# AstroEQ_SMD_V4_8_EQ5.net
KiCad netlist of a schematic drawn in EAGLE
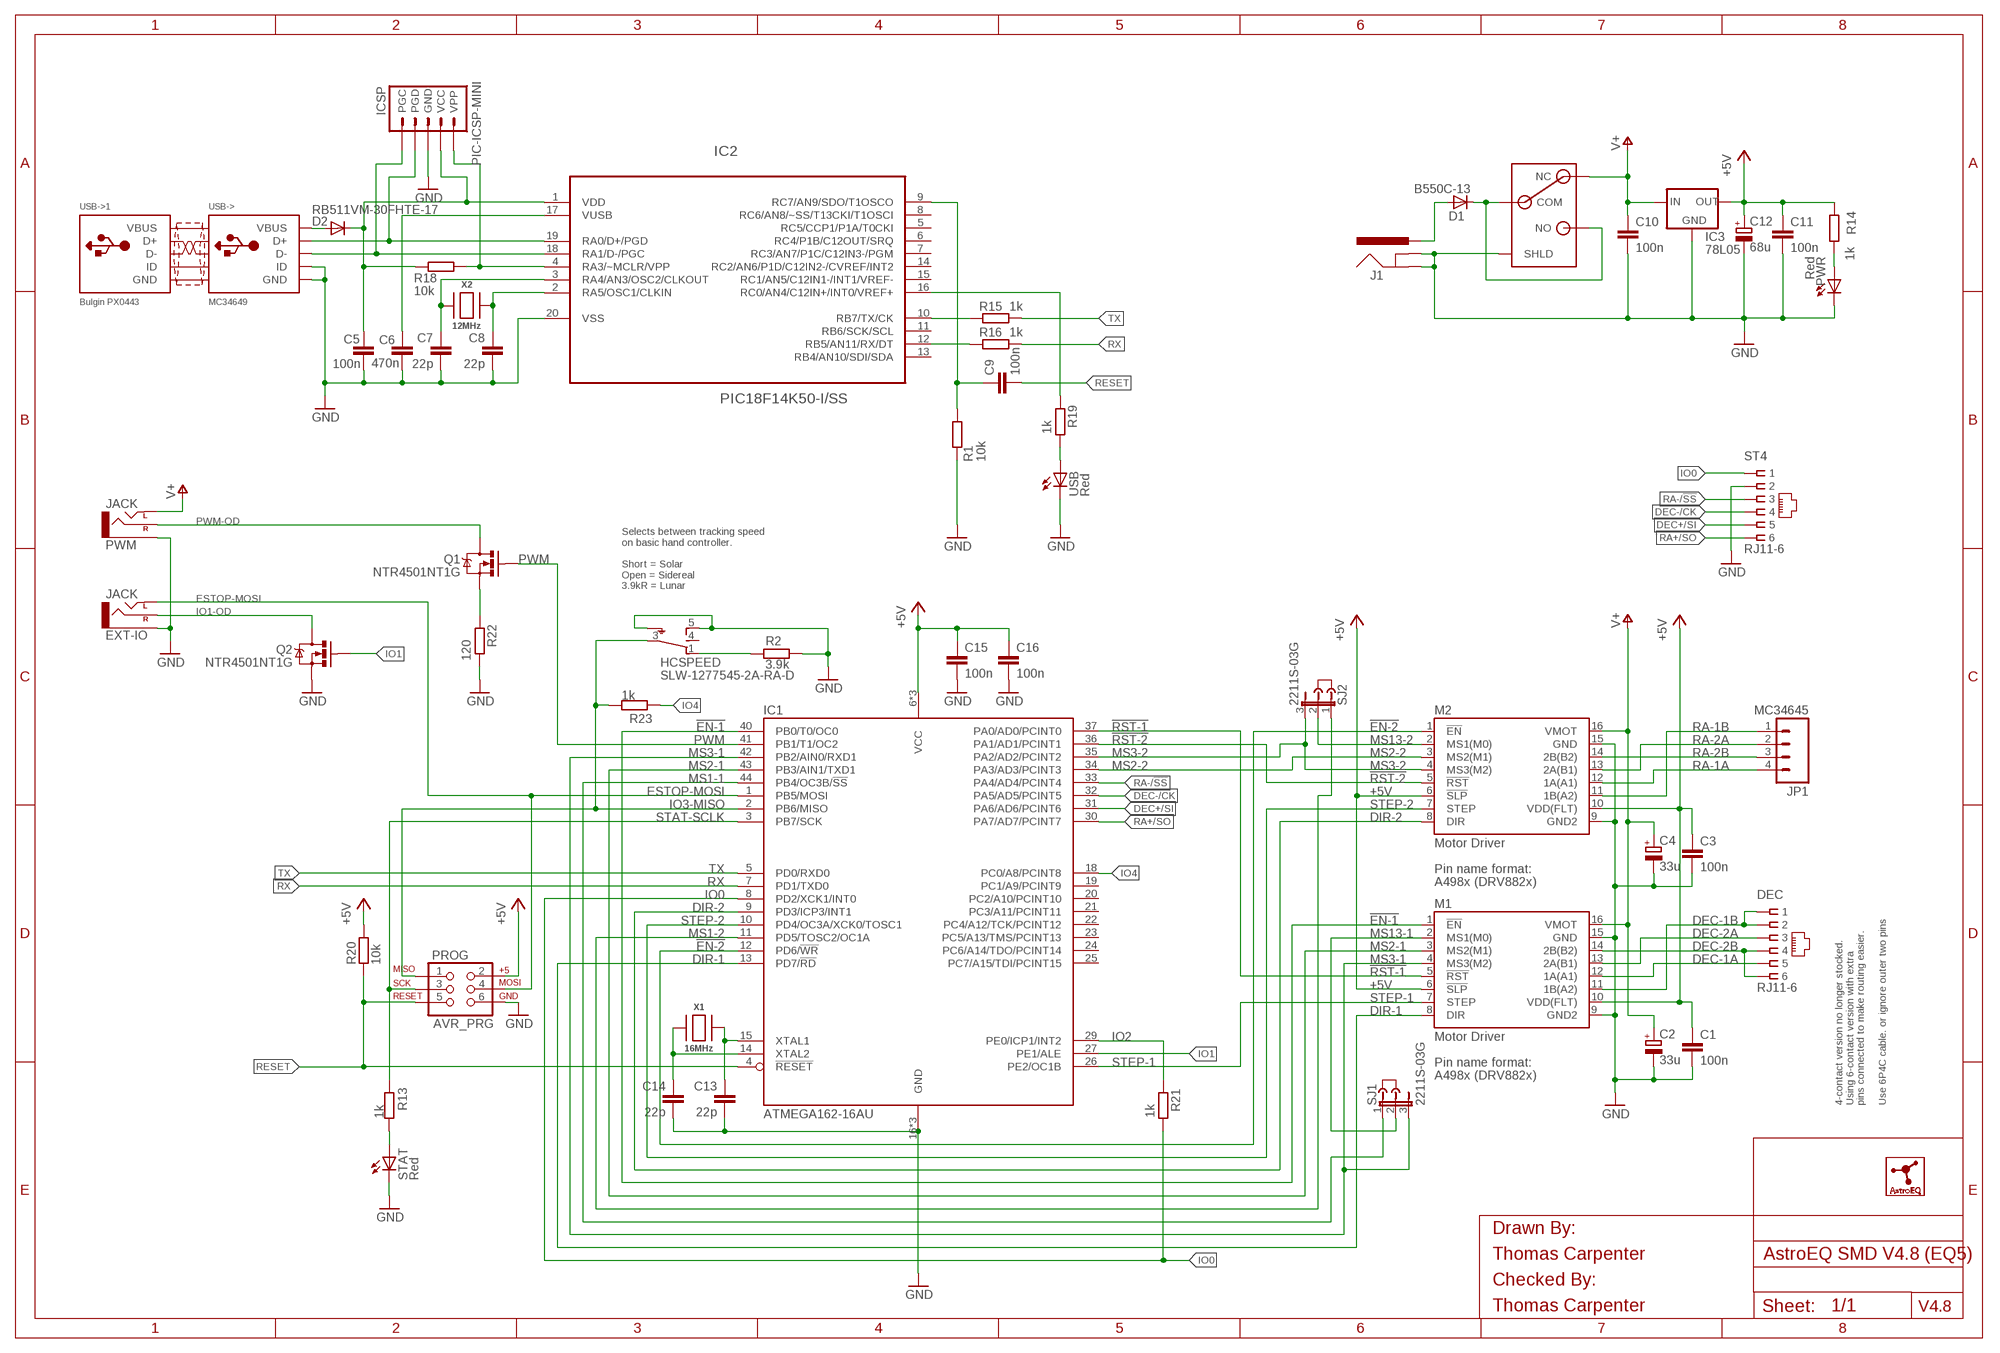
[diagram p0: schematic, sheet 1]

(export (version "E")
  (design (tool "Eeschema 10.0.6"))
  (components
    (comp (ref "C1")
      (value "100n")
      (footprint "eagle-import:C0603")
      (fields (field (name "MF") "MULTICOMP") (field (name "MPN") "MC0603F104Z250CT"))
      (libsource (lib "eagle-import") (part "C-EUC0603"))
    )
    (comp (ref "C2")
      (value "33u")
      (footprint "eagle-import:SMC_C")
      (fields (field (name "MF") "KEMET") (field (name "MPN") "T491C336K025AT"))
      (libsource (lib "eagle-import") (part "CPOL-EUSMCC"))
    )
    (comp (ref "C3")
      (value "100n")
      (footprint "eagle-import:C0603")
      (fields (field (name "MF") "MULTICOMP") (field (name "MPN") "MC0603F104Z250CT"))
      (libsource (lib "eagle-import") (part "C-EUC0603"))
    )
    (comp (ref "C4")
      (value "33u")
      (footprint "eagle-import:SMC_C")
      (fields (field (name "MF") "KEMET") (field (name "MPN") "T491C336K025AT"))
      (libsource (lib "eagle-import") (part "CPOL-EUSMCC"))
    )
    (comp (ref "C5")
      (value "100n")
      (footprint "eagle-import:C0603")
      (fields (field (name "MF") "MULTICOMP") (field (name "MPN") "MC0603F104Z250CT"))
      (libsource (lib "eagle-import") (part "C-EUC0603"))
    )
    (comp (ref "C6")
      (value "470n")
      (footprint "eagle-import:C0603")
      (fields (field (name "MF") "MULTICOMP") (field (name "MPN") "MC0603F474Z160CT"))
      (libsource (lib "eagle-import") (part "C-EUC0603"))
    )
    (comp (ref "C7")
      (value "22p")
      (footprint "eagle-import:C0603")
      (fields (field (name "MF") "MULTICOMP") (field (name "MPN") "MC0603N220J500CT"))
      (libsource (lib "eagle-import") (part "C-EUC0603"))
    )
    (comp (ref "C8")
      (value "22p")
      (footprint "eagle-import:C0603")
      (fields (field (name "MF") "MULTICOMP") (field (name "MPN") "MC0603N220J500CT"))
      (libsource (lib "eagle-import") (part "C-EUC0603"))
    )
    (comp (ref "C9")
      (value "100n")
      (footprint "eagle-import:C0603")
      (fields (field (name "MF") "MULTICOMP") (field (name "MPN") "MC0603F104Z250CT"))
      (libsource (lib "eagle-import") (part "C-EUC0603"))
    )
    (comp (ref "C10")
      (value "100n")
      (footprint "eagle-import:C0603")
      (fields (field (name "MF") "MULTICOMP") (field (name "MPN") "MC0603F104Z250CT"))
      (libsource (lib "eagle-import") (part "C-EUC0603"))
    )
    (comp (ref "C11")
      (value "100n")
      (footprint "eagle-import:C0603")
      (fields (field (name "MF") "MULTICOMP") (field (name "MPN") "MC0603F104Z250CT"))
      (libsource (lib "eagle-import") (part "C-EUC0603"))
    )
    (comp (ref "C12")
      (value "68u")
      (footprint "eagle-import:SMC_C")
      (fields (field (name "MF") "AVX") (field (name "MPN") "TPSC686K016R0125"))
      (libsource (lib "eagle-import") (part "CPOL-EUSMCC"))
    )
    (comp (ref "C13")
      (value "22p")
      (footprint "eagle-import:C0603")
      (fields (field (name "MF") "MULTICOMP") (field (name "MPN") "MC0603N220J500CT"))
      (libsource (lib "eagle-import") (part "C-EUC0603"))
    )
    (comp (ref "C14")
      (value "22p")
      (footprint "eagle-import:C0603")
      (fields (field (name "MF") "MULTICOMP") (field (name "MPN") "MC0603N220J500CT"))
      (libsource (lib "eagle-import") (part "C-EUC0603"))
    )
    (comp (ref "C15")
      (value "100n")
      (footprint "eagle-import:C0603")
      (fields (field (name "MF") "MULTICOMP") (field (name "MPN") "MC0603F104Z250CT"))
      (libsource (lib "eagle-import") (part "C-EUC0603"))
    )
    (comp (ref "C16")
      (value "100n")
      (footprint "eagle-import:C0603")
      (fields (field (name "MF") "MULTICOMP") (field (name "MPN") "MC0603F104Z250CT"))
      (libsource (lib "eagle-import") (part "C-EUC0603"))
    )
    (comp (ref "D1")
      (value "B550C-13")
      (footprint "eagle-import:SMC")
      (fields (field (name "MF") "DIODES INC.") (field (name "MPN") "B550C-13-F"))
      (libsource (lib "eagle-import") (part "DIODE-SMC"))
    )
    (comp (ref "D2")
      (value "RB511VM-30FHTE-17")
      (footprint "eagle-import:SOD-323")
      (fields (field (name "MF") "ROHM"))
      (libsource (lib "eagle-import") (part "DIODESOD"))
    )
    (comp (ref "DEC")
      (value "RJ11-6")
      (footprint "eagle-import:RJ11-NO_SHIELD")
      (fields
        (field (name "MF") "TYCO ELECTRONICS")
        (field (name "MPN") "RJ11-2L-B")
        (field (name "MF_1") "MOLEX")
        (field (name "MPN_1") "95503-2661")
        (field (name "OC_FARNELL") "1620210")
      )
      (libsource (lib "eagle-import") (part "RJ11-2L-B"))
    )
    (comp (ref "EXT-IO")
      (value "JACK")
      (footprint "eagle-import:AUDIO-JACK-3.5MM-VERT")
      (fields (field (name "MANUFACTURER") "LUMBERG") (field (name "MPN") "1502 01"))
      (libsource (lib "eagle-import") (part "AUDIO-JACKVERT"))
    )
    (comp (ref "HCSPEED")
      (value "SLW-1277545-2A-RA-D")
      (footprint "eagle-import:SLW-127")
      (libsource (lib "eagle-import") (part "SLW-1277545-2A-RA-D"))
    )
    (comp (ref "IC1")
      (value "ATMEGA162-16AU")
      (footprint "eagle-import:TQFP44")
      (fields (field (name "MF") "ATMEL"))
      (libsource (lib "eagle-import") (part "ATMEGA162-16AU"))
    )
    (comp (ref "IC2")
      (value "PIC18F14K50-I/SS")
      (footprint "eagle-import:SS20")
      (fields (field (name "MF") "MICROCHIP"))
      (libsource (lib "eagle-import") (part "PIC18F14K50/SS-I"))
    )
    (comp (ref "IC3")
      (value "78L05")
      (footprint "eagle-import:SOT23")
      (fields (field (name "MF") "TAIWAN SEMICONDUCTOR") (field (name "MPN") "TS78L05CX RFG"))
      (libsource (lib "eagle-import") (part "78LXXSOT-23"))
    )
    (comp (ref "ICSP")
      (value "PIC-ICSP-MINI")
      (footprint "eagle-import:PIC-ICSP-MINI")
      (libsource (lib "eagle-import") (part "PIC-ICSP-MINI"))
    )
    (comp (ref "J1")
      (value "POWER_JACKPANEL")
      (footprint "eagle-import:POWER_JACK_PANEL")
      (fields (field (name "MF") "SWITCHCRAFT") (field (name "MPN") "PCL712AS"))
      (libsource (lib "eagle-import") (part "POWER_JACKPANEL"))
    )
    (comp (ref "J2")
      (value "DNI")
      (footprint "eagle-import:JUMP")
      (fields (field (name "MF") "3M") (field (name "MPN") "969102-0000-DA"))
      (libsource (lib "eagle-import") (part "JUMPER"))
    )
    (comp (ref "J3")
      (value "DNI")
      (footprint "eagle-import:JUMP")
      (fields (field (name "MF") "3M") (field (name "MPN") "969102-0000-DA"))
      (libsource (lib "eagle-import") (part "JUMPER"))
    )
    (comp (ref "JP1")
      (value "MC34645")
      (footprint "eagle-import:MOLEX-1X4")
      (fields (field (name "MF") "MULTICOMP"))
      (libsource (lib "eagle-import") (part "M04POLAR"))
    )
    (comp (ref "LOGO1")
      (value "ASTROEQ5MM")
      (footprint "eagle-import:ASTROEQ-SMALL")
      (libsource (lib "eagle-import") (part "ASTROEQ5MM"))
    )
    (comp (ref "M1")
      (value "Motor Driver")
      (footprint "eagle-import:DIP16-W")
      (fields (field (name "MF") "SAMTEC") (field (name "MPN") "CES-116-01-T-S"))
      (libsource (lib "eagle-import") (part "A4983CARRIER"))
    )
    (comp (ref "M2")
      (value "Motor Driver")
      (footprint "eagle-import:DIP16-W")
      (fields (field (name "MF") "SAMTEC") (field (name "MPN") "CES-116-01-T-S"))
      (libsource (lib "eagle-import") (part "A4983CARRIER"))
    )
    (comp (ref "PROG")
      (value "AVR_PRG")
      (footprint "eagle-import:2X3")
      (fields (field (name "MF") "AMP - TE CONNECTIVITY") (field (name "MPN") "826632-3"))
      (libsource (lib "eagle-import") (part "AVR_SPI_PRG_6PTH"))
    )
    (comp (ref "PWM")
      (value "JACK")
      (footprint "eagle-import:AUDIO-JACK-3.5MM-VERT")
      (fields (field (name "MANUFACTURER") "LUMBERG") (field (name "MPN") "1502 01"))
      (libsource (lib "eagle-import") (part "AUDIO-JACKVERT"))
    )
    (comp (ref "PWR")
      (value "Red")
      (footprint "eagle-import:LED3MM")
      (fields (field (name "MF") "KINGBRIGHT") (field (name "MPN") "L-424HDT"))
      (libsource (lib "eagle-import") (part "LED3MM"))
    )
    (comp (ref "PWR-SW")
      (value "SWITCH")
      (footprint "eagle-import:SPST")
      (fields (field (name "MF") "TE CONNECTIVITY") (field (name "MPN") "AE101J1V3B004"))
      (libsource (lib "eagle-import") (part "SWITCH"))
    )
    (comp (ref "Q1")
      (value "NTR4501NT1G")
      (footprint "eagle-import:SOT23-3")
      (fields (field (name "MF") "ON SEMICONDUCTOR"))
      (libsource (lib "eagle-import") (part "MOSFET-NCHANNELSMD"))
    )
    (comp (ref "Q2")
      (value "NTR4501NT1G")
      (footprint "eagle-import:SOT23-3")
      (fields (field (name "MF") "ON SEMICONDUCTOR"))
      (libsource (lib "eagle-import") (part "MOSFET-NCHANNELSMD"))
    )
    (comp (ref "R1")
      (value "10k")
      (footprint "eagle-import:R0603")
      (fields (field (name "MF") "MULTICOMP") (field (name "MPN") "MCWR06X1002FTL"))
      (libsource (lib "eagle-import") (part "R-EU_R0603"))
    )
    (comp (ref "R2")
      (value "3.9k")
      (footprint "eagle-import:R0603")
      (fields (field (name "MF") "MULTICOMP") (field (name "MPN") "MCWR06X1001FTL"))
      (libsource (lib "eagle-import") (part "R-EU_R0603"))
    )
    (comp (ref "R13")
      (value "1k")
      (footprint "eagle-import:R0603")
      (fields (field (name "MF") "MULTICOMP") (field (name "MPN") "MCWR06X1001FTL"))
      (libsource (lib "eagle-import") (part "R-EU_R0603"))
    )
    (comp (ref "R14")
      (value "1k")
      (footprint "eagle-import:R0603")
      (fields (field (name "MF") "MULTICOMP") (field (name "MPN") "MCWR06X1001FTL"))
      (libsource (lib "eagle-import") (part "R-EU_R0603"))
    )
    (comp (ref "R15")
      (value "1k")
      (footprint "eagle-import:R0603")
      (fields (field (name "MF") "MULTICOMP") (field (name "MPN") "MCWR06X1001FTL"))
      (libsource (lib "eagle-import") (part "R-EU_R0603"))
    )
    (comp (ref "R16")
      (value "1k")
      (footprint "eagle-import:R0603")
      (fields (field (name "MF") "MULTICOMP") (field (name "MPN") "MCWR06X1001FTL"))
      (libsource (lib "eagle-import") (part "R-EU_R0603"))
    )
    (comp (ref "R18")
      (value "10k")
      (footprint "eagle-import:R0603")
      (fields (field (name "MF") "MULTICOMP") (field (name "MPN") "MCWR06X1002FTL"))
      (libsource (lib "eagle-import") (part "R-EU_R0603"))
    )
    (comp (ref "R19")
      (value "1k")
      (footprint "eagle-import:R0603")
      (fields (field (name "MF") "MULTICOMP") (field (name "MPN") "MCWR06X1001FTL"))
      (libsource (lib "eagle-import") (part "R-EU_R0603"))
    )
    (comp (ref "R20")
      (value "10k")
      (footprint "eagle-import:R0603")
      (fields (field (name "MF") "MULTICOMP") (field (name "MPN") "MCWR06X1002FTL"))
      (libsource (lib "eagle-import") (part "R-EU_R0603"))
    )
    (comp (ref "R21")
      (value "1k")
      (footprint "eagle-import:R0603")
      (fields (field (name "MF") "MULTICOMP") (field (name "MPN") "MCWR06X1001FTL"))
      (libsource (lib "eagle-import") (part "R-EU_R0603"))
    )
    (comp (ref "R22")
      (value "120")
      (footprint "eagle-import:R0805")
      (fields (field (name "MF") "MULTICOMP") (field (name "MPN") "MCWR08X1200FTL"))
      (libsource (lib "eagle-import") (part "R-EU_R0805"))
    )
    (comp (ref "R23")
      (value "1k")
      (footprint "eagle-import:R0603")
      (fields (field (name "MF") "MULTICOMP") (field (name "MPN") "MCWR06X1001FTL"))
      (libsource (lib "eagle-import") (part "R-EU_R0603"))
    )
    (comp (ref "SJ1")
      (value "2211S-03G")
      (footprint "eagle-import:JP2")
      (fields (field (name "MF") "MULTICOMP"))
      (libsource (lib "eagle-import") (part "JP2E"))
    )
    (comp (ref "SJ2")
      (value "2211S-03G")
      (footprint "eagle-import:JP2")
      (fields (field (name "MF") "MULTICOMP"))
      (libsource (lib "eagle-import") (part "JP2E"))
    )
    (comp (ref "ST4")
      (value "RJ11-6")
      (footprint "eagle-import:RJ11-NO_SHIELD")
      (fields
        (field (name "MF") "TYCO ELECTRONICS")
        (field (name "MPN") "RJ11-2L-B")
        (field (name "MF_1") "MOLEX")
        (field (name "MPN_1") "95503-2661")
        (field (name "OC_FARNELL") "1620210")
      )
      (libsource (lib "eagle-import") (part "RJ11-2L-B"))
    )
    (comp (ref "STAT")
      (value "Red")
      (footprint "eagle-import:LED3MM")
      (fields (field (name "MF") "KINGBRIGHT") (field (name "MPN") "L-424HDT"))
      (libsource (lib "eagle-import") (part "LED3MM"))
    )
    (comp (ref "USB")
      (value "Red")
      (footprint "eagle-import:LED3MM")
      (fields (field (name "MF") "KINGBRIGHT") (field (name "MPN") "L-424HDT"))
      (libsource (lib "eagle-import") (part "LED3MM"))
    )
    (comp (ref "USB->")
      (value "MC34649")
      (footprint "eagle-import:22-23-2051")
      (fields (field (name "MF") "MULTICOMP") (field (name "MPN") "MC34647"))
      (libsource (lib "eagle-import") (part "USBBULGINWIRE"))
    )
    (comp (ref "X1")
      (value "16MHz")
      (footprint "eagle-import:NX5032")
      (fields (field (name "MF") "TXC") (field (name "MPN") "7A-16.000MAAJ-T"))
      (libsource (lib "eagle-import") (part "XTALNX5032"))
    )
    (comp (ref "X2")
      (value "12MHz")
      (footprint "eagle-import:NX5032")
      (fields (field (name "MF") "TXC") (field (name "MPN") "7A-12.000MAAJ-T"))
      (libsource (lib "eagle-import") (part "XTALNX5032"))
    )
  )
  (nets
    (net (code "1") (name "+5V") (class "Default")
      (node (ref "C1") (pin "1") (pinfunction "1_1") (pintype "passive"))
      (node (ref "C11") (pin "1") (pinfunction "1_1") (pintype "passive"))
      (node (ref "C12") (pin "+") (pinfunction "+_+") (pintype "passive"))
      (node (ref "C15") (pin "1") (pinfunction "1_1") (pintype "passive"))
      (node (ref "C16") (pin "1") (pinfunction "1_1") (pintype "passive"))
      (node (ref "C3") (pin "1") (pinfunction "1_1") (pintype "passive"))
      (node (ref "IC1") (pin "17") (pinfunction "VCC_17") (pintype "power_in"))
      (node (ref "IC1") (pin "38") (pinfunction "VCC_38") (pintype "power_in"))
      (node (ref "IC1") (pin "6") (pinfunction "VCC_6") (pintype "power_in"))
      (node (ref "IC3") (pin "1") (pinfunction "OUT_1") (pintype "passive"))
      (node (ref "M1") (pin "10") (pinfunction "VDD(FLT)_10") (pintype "power_in"))
      (node (ref "M1") (pin "6") (pinfunction "~{SLP}_6") (pintype "input"))
      (node (ref "M2") (pin "10") (pinfunction "VDD(FLT)_10") (pintype "power_in"))
      (node (ref "M2") (pin "6") (pinfunction "~{SLP}_6") (pintype "input"))
      (node (ref "PROG") (pin "2") (pinfunction "2_2") (pintype "passive"))
      (node (ref "R14") (pin "1") (pinfunction "1_1") (pintype "passive"))
      (node (ref "R20") (pin "2") (pinfunction "2_2") (pintype "passive"))
    )
    (net (code "2") (name "/DEC-1A") (class "Default")
      (node (ref "DEC") (pin "5") (pinfunction "5_5") (pintype "passive"))
      (node (ref "M1") (pin "12") (pinfunction "1A(A1)_12") (pintype "output"))
    )
    (net (code "3") (name "/DEC-1B") (class "Default")
      (node (ref "DEC") (pin "1") (pinfunction "1_1") (pintype "passive"))
      (node (ref "DEC") (pin "2") (pinfunction "2_2") (pintype "passive"))
      (node (ref "M1") (pin "11") (pinfunction "1B(A2)_11") (pintype "output"))
    )
    (net (code "4") (name "/DEC-2A") (class "Default")
      (node (ref "DEC") (pin "3") (pinfunction "3_3") (pintype "passive"))
      (node (ref "M1") (pin "13") (pinfunction "2A(B1)_13") (pintype "output"))
    )
    (net (code "5") (name "/DEC-2B") (class "Default")
      (node (ref "DEC") (pin "4") (pinfunction "4_4") (pintype "passive"))
      (node (ref "DEC") (pin "6") (pinfunction "6_6") (pintype "passive"))
      (node (ref "M1") (pin "14") (pinfunction "2B(B2)_14") (pintype "output"))
    )
    (net (code "6") (name "/DIR-1") (class "Default")
      (node (ref "IC1") (pin "13") (pinfunction "PD7/~{RD}_13") (pintype "bidirectional"))
      (node (ref "M1") (pin "8") (pinfunction "DIR_8") (pintype "input"))
    )
    (net (code "7") (name "/DIR-2") (class "Default")
      (node (ref "IC1") (pin "9") (pinfunction "PD3/ICP3/INT1_9") (pintype "bidirectional"))
      (node (ref "M2") (pin "8") (pinfunction "DIR_8") (pintype "input"))
    )
    (net (code "8") (name "/ESTOP-MOSI") (class "Default")
      (node (ref "EXT-IO") (pin "2") (pinfunction "LEFT_2") (pintype "bidirectional"))
      (node (ref "IC1") (pin "1") (pinfunction "PB5/MOSI_1") (pintype "bidirectional"))
      (node (ref "PROG") (pin "4") (pinfunction "4_4") (pintype "passive"))
    )
    (net (code "9") (name "/IO1-OD") (class "Default")
      (node (ref "EXT-IO") (pin "3") (pinfunction "RIGHT_3") (pintype "bidirectional"))
      (node (ref "Q2") (pin "3") (pinfunction "D_3") (pintype "passive"))
    )
    (net (code "10") (name "/IO2") (class "Default")
      (node (ref "IC1") (pin "29") (pinfunction "PE0/ICP1/INT2_29") (pintype "bidirectional"))
      (node (ref "R21") (pin "2") (pinfunction "2_2") (pintype "passive"))
    )
    (net (code "11") (name "/IO3-MISO") (class "Default")
      (node (ref "HCSPEED") (pin "3") (pinfunction "P_3") (pintype "passive"))
      (node (ref "IC1") (pin "2") (pinfunction "PB6/MISO_2") (pintype "bidirectional"))
      (node (ref "PROG") (pin "1") (pinfunction "1_1") (pintype "passive"))
      (node (ref "R23") (pin "2") (pinfunction "2_2") (pintype "passive"))
    )
    (net (code "12") (name "/MS1-1") (class "Default")
      (node (ref "IC1") (pin "44") (pinfunction "PB4/OC3B/~{SS}_44") (pintype "bidirectional"))
      (node (ref "SJ1") (pin "1") (pinfunction "1_1") (pintype "passive"))
    )
    (net (code "13") (name "/MS1-2") (class "Default")
      (node (ref "IC1") (pin "11") (pinfunction "PD5/TOSC2/OC1A_11") (pintype "bidirectional"))
      (node (ref "SJ2") (pin "1") (pinfunction "1_1") (pintype "passive"))
    )
    (net (code "14") (name "/MS2-1") (class "Default")
      (node (ref "IC1") (pin "43") (pinfunction "PB3/AIN1/TXD1_43") (pintype "bidirectional"))
      (node (ref "M1") (pin "3") (pinfunction "MS2(M1)_3") (pintype "input"))
    )
    (net (code "15") (name "/MS2-2") (class "Default")
      (node (ref "IC1") (pin "34") (pinfunction "PA3/AD3/PCINT3_34") (pintype "bidirectional"))
      (node (ref "M2") (pin "3") (pinfunction "MS2(M1)_3") (pintype "input"))
    )
    (net (code "16") (name "/MS3-1") (class "Default")
      (node (ref "IC1") (pin "42") (pinfunction "PB2/AIN0/RXD1_42") (pintype "bidirectional"))
      (node (ref "M1") (pin "4") (pinfunction "MS3(M2)_4") (pintype "input"))
      (node (ref "SJ1") (pin "3") (pinfunction "3_3") (pintype "passive"))
    )
    (net (code "17") (name "/MS3-2") (class "Default")
      (node (ref "IC1") (pin "35") (pinfunction "PA2/AD2/PCINT2_35") (pintype "bidirectional"))
      (node (ref "M2") (pin "4") (pinfunction "MS3(M2)_4") (pintype "input"))
      (node (ref "SJ2") (pin "3") (pinfunction "3_3") (pintype "passive"))
    )
    (net (code "18") (name "/MS13-1") (class "Default")
      (node (ref "M1") (pin "2") (pinfunction "MS1(M0)_2") (pintype "input"))
      (node (ref "SJ1") (pin "2") (pinfunction "2_2") (pintype "passive"))
    )
    (net (code "19") (name "/MS13-2") (class "Default")
      (node (ref "M2") (pin "2") (pinfunction "MS1(M0)_2") (pintype "input"))
      (node (ref "SJ2") (pin "2") (pinfunction "2_2") (pintype "passive"))
    )
    (net (code "20") (name "/PWM") (class "Default")
      (node (ref "IC1") (pin "41") (pinfunction "PB1/T1/OC2_41") (pintype "bidirectional"))
      (node (ref "Q1") (pin "1") (pinfunction "G_1") (pintype "passive"))
    )
    (net (code "21") (name "/PWM-OD") (class "Default")
      (node (ref "PWM") (pin "3") (pinfunction "RIGHT_3") (pintype "bidirectional"))
      (node (ref "Q1") (pin "3") (pinfunction "D_3") (pintype "passive"))
    )
    (net (code "22") (name "/RA-1A") (class "Default")
      (node (ref "JP1") (pin "4") (pinfunction "4_4") (pintype "passive"))
      (node (ref "M2") (pin "12") (pinfunction "1A(A1)_12") (pintype "output"))
    )
    (net (code "23") (name "/RA-1B") (class "Default")
      (node (ref "JP1") (pin "1") (pinfunction "1_1") (pintype "passive"))
      (node (ref "M2") (pin "11") (pinfunction "1B(A2)_11") (pintype "output"))
    )
    (net (code "24") (name "/RA-2A") (class "Default")
      (node (ref "JP1") (pin "2") (pinfunction "2_2") (pintype "passive"))
      (node (ref "M2") (pin "13") (pinfunction "2A(B1)_13") (pintype "output"))
    )
    (net (code "25") (name "/RA-2B") (class "Default")
      (node (ref "JP1") (pin "3") (pinfunction "3_3") (pintype "passive"))
      (node (ref "M2") (pin "14") (pinfunction "2B(B2)_14") (pintype "output"))
    )
    (net (code "26") (name "/RA-{slash}~{SS}") (class "Default")
      (node (ref "IC1") (pin "33") (pinfunction "PA4/AD4/PCINT4_33") (pintype "bidirectional"))
      (node (ref "ST4") (pin "3") (pinfunction "3_3") (pintype "passive"))
    )
    (net (code "27") (name "/STAT-SCLK") (class "Default")
      (node (ref "IC1") (pin "3") (pinfunction "PB7/SCK_3") (pintype "bidirectional"))
      (node (ref "PROG") (pin "3") (pinfunction "3_3") (pintype "passive"))
      (node (ref "R13") (pin "1") (pinfunction "1_1") (pintype "passive"))
    )
    (net (code "28") (name "/STEP-1") (class "Default")
      (node (ref "IC1") (pin "26") (pinfunction "PE2/OC1B_26") (pintype "bidirectional"))
      (node (ref "M1") (pin "7") (pinfunction "STEP_7") (pintype "input"))
    )
    (net (code "29") (name "/STEP-2") (class "Default")
      (node (ref "IC1") (pin "10") (pinfunction "PD4/OC3A/XCK0/TOSC1_10") (pintype "bidirectional"))
      (node (ref "M2") (pin "7") (pinfunction "STEP_7") (pintype "input"))
    )
    (net (code "30") (name "/~{EN-1}") (class "Default")
      (node (ref "IC1") (pin "40") (pinfunction "PB0/T0/OC0_40") (pintype "bidirectional"))
      (node (ref "M1") (pin "1") (pinfunction "~{EN}_1") (pintype "input"))
    )
    (net (code "31") (name "/~{EN-2}") (class "Default")
      (node (ref "IC1") (pin "12") (pinfunction "PD6/~{WR}_12") (pintype "bidirectional"))
      (node (ref "M2") (pin "1") (pinfunction "~{EN}_1") (pintype "input"))
    )
    (net (code "32") (name "/~{RST-1}") (class "Default")
      (node (ref "IC1") (pin "37") (pinfunction "PA0/AD0/PCINT0_37") (pintype "bidirectional"))
      (node (ref "M1") (pin "5") (pinfunction "~{RST}_5") (pintype "input"))
    )
    (net (code "33") (name "/~{RST-2}") (class "Default")
      (node (ref "IC1") (pin "36") (pinfunction "PA1/AD1/PCINT1_36") (pintype "bidirectional"))
      (node (ref "M2") (pin "5") (pinfunction "~{RST}_5") (pintype "input"))
    )
    (net (code "34") (name "DEC+{slash}SI") (class "Default")
      (node (ref "IC1") (pin "31") (pinfunction "PA6/AD6/PCINT6_31") (pintype "bidirectional"))
      (node (ref "ST4") (pin "5") (pinfunction "5_5") (pintype "passive"))
    )
    (net (code "35") (name "DEC-{slash}CK") (class "Default")
      (node (ref "IC1") (pin "32") (pinfunction "PA5/AD5/PCINT5_32") (pintype "bidirectional"))
      (node (ref "ST4") (pin "4") (pinfunction "4_4") (pintype "passive"))
    )
    (net (code "36") (name "GND") (class "Default")
      (node (ref "C1") (pin "2") (pinfunction "2_2") (pintype "passive"))
      (node (ref "C10") (pin "2") (pinfunction "2_2") (pintype "passive"))
      (node (ref "C11") (pin "2") (pinfunction "2_2") (pintype "passive"))
      (node (ref "C12") (pin "-") (pinfunction "-_-") (pintype "passive"))
      (node (ref "C13") (pin "2") (pinfunction "2_2") (pintype "passive"))
      (node (ref "C14") (pin "2") (pinfunction "2_2") (pintype "passive"))
      (node (ref "C15") (pin "2") (pinfunction "2_2") (pintype "passive"))
      (node (ref "C16") (pin "2") (pinfunction "2_2") (pintype "passive"))
      (node (ref "C2") (pin "-") (pinfunction "-_-") (pintype "passive"))
      (node (ref "C3") (pin "2") (pinfunction "2_2") (pintype "passive"))
      (node (ref "C4") (pin "-") (pinfunction "-_-") (pintype "passive"))
      (node (ref "C5") (pin "2") (pinfunction "2_2") (pintype "passive"))
      (node (ref "C6") (pin "1") (pinfunction "1_1") (pintype "passive"))
      (node (ref "C7") (pin "2") (pinfunction "2_2") (pintype "passive"))
      (node (ref "C8") (pin "2") (pinfunction "2_2") (pintype "passive"))
      (node (ref "EXT-IO") (pin "1") (pinfunction "SLEEVE_1") (pintype "bidirectional"))
      (node (ref "HCSPEED") (pin "5") (pinfunction "O_5") (pintype "passive"))
      (node (ref "HCSPEED") (pin "S1") (pinfunction "SH_S1") (pintype "passive"))
      (node (ref "HCSPEED") (pin "S2") (pinfunction "SH_S2") (pintype "passive"))
      (node (ref "IC1") (pin "16") (pinfunction "GND_16") (pintype "power_in"))
      (node (ref "IC1") (pin "28") (pinfunction "GND_28") (pintype "power_in"))
      (node (ref "IC1") (pin "39") (pinfunction "GND_39") (pintype "power_in"))
      (node (ref "IC2") (pin "20") (pinfunction "VSS_20") (pintype "power_in"))
      (node (ref "IC3") (pin "3") (pinfunction "GND_3") (pintype "input"))
      (node (ref "ICSP") (pin "3") (pinfunction "GND_3") (pintype "passive"))
      (node (ref "J1") (pin "SHUNT") (pinfunction "GNDBREAK_SHUNT") (pintype "bidirectional"))
      (node (ref "J1") (pin "SLEEVE") (pinfunction "GND_SLEEVE") (pintype "bidirectional"))
      (node (ref "M1") (pin "15") (pinfunction "GND_15") (pintype "power_in"))
      (node (ref "M1") (pin "9") (pinfunction "GND2_9") (pintype "power_in"))
      (node (ref "M2") (pin "15") (pinfunction "GND_15") (pintype "power_in"))
      (node (ref "M2") (pin "9") (pinfunction "GND2_9") (pintype "power_in"))
      (node (ref "PROG") (pin "6") (pinfunction "6_6") (pintype "passive"))
      (node (ref "PWM") (pin "1") (pinfunction "SLEEVE_1") (pintype "bidirectional"))
      (node (ref "PWR") (pin "K") (pinfunction "C_K") (pintype "passive"))
      (node (ref "PWR-SW") (pin "S1") (pinfunction "SHLD_S1") (pintype "bidirectional"))
      (node (ref "PWR-SW") (pin "S2") (pinfunction "SHLD_S2") (pintype "bidirectional"))
      (node (ref "PWR-SW") (pin "S3") (pinfunction "SHLD_S3") (pintype "bidirectional"))
      (node (ref "PWR-SW") (pin "S4") (pinfunction "SHLD_S4") (pintype "bidirectional"))
      (node (ref "Q2") (pin "2") (pinfunction "S_2") (pintype "passive"))
      (node (ref "R1") (pin "2") (pinfunction "2_2") (pintype "passive"))
      (node (ref "R2") (pin "2") (pinfunction "2_2") (pintype "passive"))
      (node (ref "R22") (pin "1") (pinfunction "1_1") (pintype "passive"))
      (node (ref "ST4") (pin "2") (pinfunction "2_2") (pintype "passive"))
      (node (ref "STAT") (pin "K") (pinfunction "C_K") (pintype "passive"))
      (node (ref "USB") (pin "K") (pinfunction "C_K") (pintype "passive"))
      (node (ref "USB->") (pin "4") (pinfunction "GND_4") (pintype "power_in"))
      (node (ref "USB->") (pin "5") (pinfunction "ID_5") (pintype "bidirectional"))
    )
    (net (code "37") (name "IO0") (class "Default")
      (node (ref "IC1") (pin "8") (pinfunction "PD2/XCK1/INT0_8") (pintype "bidirectional"))
      (node (ref "R21") (pin "1") (pinfunction "1_1") (pintype "passive"))
      (node (ref "ST4") (pin "1") (pinfunction "1_1") (pintype "passive"))
    )
    (net (code "38") (name "IO1") (class "Default")
      (node (ref "IC1") (pin "27") (pinfunction "PE1/ALE_27") (pintype "bidirectional"))
      (node (ref "Q2") (pin "1") (pinfunction "G_1") (pintype "passive"))
    )
    (net (code "39") (name "IO4") (class "Default")
      (node (ref "IC1") (pin "18") (pinfunction "PC0/A8/PCINT8_18") (pintype "bidirectional"))
      (node (ref "R23") (pin "1") (pinfunction "1_1") (pintype "passive"))
    )
    (net (code "40") (name "Net-(D1-PadC)") (class "Default")
      (node (ref "D1") (pin "C") (pinfunction "C_C") (pintype "passive"))
      (node (ref "PWR-SW") (pin "COM") (pinfunction "COM_COM") (pintype "passive"))
      (node (ref "PWR-SW") (pin "NO") (pinfunction "NO_NO") (pintype "passive"))
    )
    (net (code "41") (name "Net-(D2-A)") (class "Default")
      (node (ref "D2") (pin "2") (pinfunction "A_2") (pintype "passive"))
      (node (ref "USB->") (pin "1") (pinfunction "VBUS_1") (pintype "power_in"))
    )
    (net (code "42") (name "Net-(D2-C)") (class "Default")
      (node (ref "C5") (pin "1") (pinfunction "1_1") (pintype "passive"))
      (node (ref "D2") (pin "1") (pinfunction "C_1") (pintype "passive"))
      (node (ref "IC2") (pin "1") (pinfunction "VDD_1") (pintype "power_in"))
      (node (ref "ICSP") (pin "2") (pinfunction "VCC_2") (pintype "passive"))
      (node (ref "R18") (pin "2") (pinfunction "2_2") (pintype "passive"))
    )
    (net (code "43") (name "Net-(HCSPEED-S)") (class "Default")
      (node (ref "HCSPEED") (pin "1") (pinfunction "S_1") (pintype "passive"))
      (node (ref "R2") (pin "1") (pinfunction "1_1") (pintype "passive"))
    )
    (net (code "44") (name "Net-(IC1-XTAL1)") (class "Default")
      (node (ref "C13") (pin "1") (pinfunction "1_1") (pintype "passive"))
      (node (ref "IC1") (pin "15") (pinfunction "XTAL1_15") (pintype "input"))
      (node (ref "X1") (pin "1") (pinfunction "P$1_1") (pintype "bidirectional"))
    )
    (net (code "45") (name "Net-(IC1-XTAL2)") (class "Default")
      (node (ref "C14") (pin "1") (pinfunction "1_1") (pintype "passive"))
      (node (ref "IC1") (pin "14") (pinfunction "XTAL2_14") (pintype "input"))
      (node (ref "X1") (pin "2") (pinfunction "P$2_2") (pintype "bidirectional"))
    )
    (net (code "46") (name "Net-(IC2-RA0{slash}D+{slash}PGD)") (class "Default")
      (node (ref "IC2") (pin "19") (pinfunction "RA0/D+/PGD_19") (pintype "bidirectional"))
      (node (ref "ICSP") (pin "4") (pinfunction "PGD_4") (pintype "passive"))
      (node (ref "USB->") (pin "3") (pinfunction "D+_3") (pintype "bidirectional"))
    )
    (net (code "47") (name "Net-(IC2-RA1{slash}D-{slash}PGC)") (class "Default")
      (node (ref "IC2") (pin "18") (pinfunction "RA1/D-/PGC_18") (pintype "bidirectional"))
      (node (ref "ICSP") (pin "5") (pinfunction "PGC_5") (pintype "passive"))
      (node (ref "USB->") (pin "2") (pinfunction "D-_2") (pintype "bidirectional"))
    )
    (net (code "48") (name "Net-(IC2-RA3{slash}~{MCLR{slash}VPP})") (class "Default")
      (node (ref "IC2") (pin "4") (pinfunction "RA3/~{MCLR/VPP}_4") (pintype "input"))
      (node (ref "ICSP") (pin "1") (pinfunction "VPP_1") (pintype "passive"))
      (node (ref "R18") (pin "1") (pinfunction "1_1") (pintype "passive"))
    )
    (net (code "49") (name "Net-(IC2-RA4{slash}AN3{slash}OSC2{slash}CLKOUT)") (class "Default")
      (node (ref "C7") (pin "1") (pinfunction "1_1") (pintype "passive"))
      (node (ref "IC2") (pin "3") (pinfunction "RA4/AN3/OSC2/CLKOUT_3") (pintype "bidirectional"))
      (node (ref "X2") (pin "1") (pinfunction "P$1_1") (pintype "bidirectional"))
    )
    (net (code "50") (name "Net-(IC2-RA5{slash}OSC1{slash}CLKIN)") (class "Default")
      (node (ref "C8") (pin "1") (pinfunction "1_1") (pintype "passive"))
      (node (ref "IC2") (pin "2") (pinfunction "RA5/OSC1/CLKIN_2") (pintype "bidirectional"))
      (node (ref "X2") (pin "2") (pinfunction "P$2_2") (pintype "bidirectional"))
    )
    (net (code "51") (name "Net-(IC2-RB5{slash}AN11{slash}RX{slash}DT)") (class "Default")
      (node (ref "IC2") (pin "12") (pinfunction "RB5/AN11/RX/DT_12") (pintype "bidirectional"))
      (node (ref "R16") (pin "2") (pinfunction "2_2") (pintype "passive"))
    )
    (net (code "52") (name "Net-(IC2-RB7{slash}TX{slash}CK)") (class "Default")
      (node (ref "IC2") (pin "10") (pinfunction "RB7/TX/CK_10") (pintype "bidirectional"))
      (node (ref "R15") (pin "2") (pinfunction "2_2") (pintype "passive"))
    )
    (net (code "53") (name "Net-(IC2-RC0{slash}AN4{slash}C12IN+{slash}INT0{slash}VREF+)") (class "Default")
      (node (ref "IC2") (pin "16") (pinfunction "RC0/AN4/C12IN+/INT0/VREF+_16") (pintype "bidirectional"))
      (node (ref "R19") (pin "2") (pinfunction "2_2") (pintype "passive"))
    )
    (net (code "54") (name "Net-(IC2-RC7{slash}AN9{slash}SDO{slash}T1OSCO)") (class "Default")
      (node (ref "C9") (pin "1") (pinfunction "1_1") (pintype "passive"))
      (node (ref "IC2") (pin "9") (pinfunction "RC7/AN9/SDO/T1OSCO_9") (pintype "bidirectional"))
      (node (ref "R1") (pin "1") (pinfunction "1_1") (pintype "passive"))
    )
    (net (code "55") (name "Net-(IC2-VUSB)") (class "Default")
      (node (ref "C6") (pin "2") (pinfunction "2_2") (pintype "passive"))
      (node (ref "IC2") (pin "17") (pinfunction "VUSB_17") (pintype "power_in"))
    )
    (net (code "56") (name "Net-(J1-PWR)") (class "Default")
      (node (ref "D1") (pin "A") (pinfunction "A_A") (pintype "passive"))
      (node (ref "J1") (pin "CENTRE") (pinfunction "PWR_CENTRE") (pintype "bidirectional"))
    )
    (net (code "57") (name "Net-(PWR-PadA)") (class "Default")
      (node (ref "PWR") (pin "A") (pinfunction "A_A") (pintype "passive"))
      (node (ref "R14") (pin "2") (pinfunction "2_2") (pintype "passive"))
    )
    (net (code "58") (name "Net-(Q1-S)") (class "Default")
      (node (ref "Q1") (pin "2") (pinfunction "S_2") (pintype "passive"))
      (node (ref "R22") (pin "2") (pinfunction "2_2") (pintype "passive"))
    )
    (net (code "59") (name "Net-(R13-Pad2)") (class "Default")
      (node (ref "R13") (pin "2") (pinfunction "2_2") (pintype "passive"))
      (node (ref "STAT") (pin "A") (pinfunction "A_A") (pintype "passive"))
    )
    (net (code "60") (name "Net-(R19-Pad1)") (class "Default")
      (node (ref "R19") (pin "1") (pinfunction "1_1") (pintype "passive"))
      (node (ref "USB") (pin "A") (pinfunction "A_A") (pintype "passive"))
    )
    (net (code "61") (name "RA+{slash}SO") (class "Default")
      (node (ref "IC1") (pin "30") (pinfunction "PA7/AD7/PCINT7_30") (pintype "bidirectional"))
      (node (ref "ST4") (pin "6") (pinfunction "6_6") (pintype "passive"))
    )
    (net (code "62") (name "RESET") (class "Default")
      (node (ref "C9") (pin "2") (pinfunction "2_2") (pintype "passive"))
      (node (ref "IC1") (pin "4") (pinfunction "~{RESET}_4") (pintype "input"))
      (node (ref "PROG") (pin "5") (pinfunction "5_5") (pintype "passive"))
      (node (ref "R20") (pin "1") (pinfunction "1_1") (pintype "passive"))
    )
    (net (code "63") (name "RX") (class "Default")
      (node (ref "IC1") (pin "7") (pinfunction "PD1/TXD0_7") (pintype "bidirectional"))
      (node (ref "R16") (pin "1") (pinfunction "1_1") (pintype "passive"))
    )
    (net (code "64") (name "TX") (class "Default")
      (node (ref "IC1") (pin "5") (pinfunction "PD0/RXD0_5") (pintype "bidirectional"))
      (node (ref "R15") (pin "1") (pinfunction "1_1") (pintype "passive"))
    )
    (net (code "65") (name "V+") (class "Default")
      (node (ref "C10") (pin "1") (pinfunction "1_1") (pintype "passive"))
      (node (ref "C2") (pin "+") (pinfunction "+_+") (pintype "passive"))
      (node (ref "C4") (pin "+") (pinfunction "+_+") (pintype "passive"))
      (node (ref "IC3") (pin "2") (pinfunction "IN_2") (pintype "input"))
      (node (ref "M1") (pin "16") (pinfunction "VMOT_16") (pintype "power_in"))
      (node (ref "M2") (pin "16") (pinfunction "VMOT_16") (pintype "power_in"))
      (node (ref "PWM") (pin "2") (pinfunction "LEFT_2") (pintype "bidirectional"))
      (node (ref "PWR-SW") (pin "NC") (pinfunction "NC_NC") (pintype "passive"))
    )
    (net (code "66") (name "unconnected-(HCSPEED-M-Pad4)") (class "Default")
      (node (ref "HCSPEED") (pin "4") (pinfunction "M_4") (pintype "passive"))
    )
    (net (code "67") (name "unconnected-(IC1-PC1{slash}A9{slash}PCINT9-Pad19)") (class "Default")
      (node (ref "IC1") (pin "19") (pinfunction "PC1/A9/PCINT9_19") (pintype "bidirectional"))
    )
    (net (code "68") (name "unconnected-(IC1-PC2{slash}A10{slash}PCINT10-Pad20)") (class "Default")
      (node (ref "IC1") (pin "20") (pinfunction "PC2/A10/PCINT10_20") (pintype "bidirectional"))
    )
    (net (code "69") (name "unconnected-(IC1-PC3{slash}A11{slash}PCINT11-Pad21)") (class "Default")
      (node (ref "IC1") (pin "21") (pinfunction "PC3/A11/PCINT11_21") (pintype "bidirectional"))
    )
    (net (code "70") (name "unconnected-(IC1-PC4{slash}A12{slash}TCK{slash}PCINT12-Pad22)") (class "Default")
      (node (ref "IC1") (pin "22") (pinfunction "PC4/A12/TCK/PCINT12_22") (pintype "bidirectional"))
    )
    (net (code "71") (name "unconnected-(IC1-PC5{slash}A13{slash}TMS{slash}PCINT13-Pad23)") (class "Default")
      (node (ref "IC1") (pin "23") (pinfunction "PC5/A13/TMS/PCINT13_23") (pintype "bidirectional"))
    )
    (net (code "72") (name "unconnected-(IC1-PC6{slash}A14{slash}TDO{slash}PCINT14-Pad24)") (class "Default")
      (node (ref "IC1") (pin "24") (pinfunction "PC6/A14/TDO/PCINT14_24") (pintype "bidirectional"))
    )
    (net (code "73") (name "unconnected-(IC1-PC7{slash}A15{slash}TDI{slash}PCINT15-Pad25)") (class "Default")
      (node (ref "IC1") (pin "25") (pinfunction "PC7/A15/TDI/PCINT15_25") (pintype "bidirectional"))
    )
    (net (code "74") (name "unconnected-(IC2-RB4{slash}AN10{slash}SDI{slash}SDA-Pad13)") (class "Default")
      (node (ref "IC2") (pin "13") (pinfunction "RB4/AN10/SDI/SDA_13") (pintype "bidirectional"))
    )
    (net (code "75") (name "unconnected-(IC2-RB6{slash}SCK{slash}SCL-Pad11)") (class "Default")
      (node (ref "IC2") (pin "11") (pinfunction "RB6/SCK/SCL_11") (pintype "bidirectional"))
    )
    (net (code "76") (name "unconnected-(IC2-RC1{slash}AN5{slash}C12IN1-{slash}INT1{slash}VREF--Pad15)") (class "Default")
      (node (ref "IC2") (pin "15") (pinfunction "RC1/AN5/C12IN1-/INT1/VREF-_15") (pintype "bidirectional"))
    )
    (net (code "77") (name "unconnected-(IC2-RC2{slash}AN6{slash}P1D{slash}C12IN2-{slash}CVREF{slash}INT2-Pad14)") (class "Default")
      (node (ref "IC2") (pin "14") (pinfunction "RC2/AN6/P1D/C12IN2-/CVREF/INT2_14") (pintype "bidirectional"))
    )
    (net (code "78") (name "unconnected-(IC2-RC3{slash}AN7{slash}P1C{slash}C12IN3-{slash}PGM-Pad7)") (class "Default")
      (node (ref "IC2") (pin "7") (pinfunction "RC3/AN7/P1C/C12IN3-/PGM_7") (pintype "bidirectional"))
    )
    (net (code "79") (name "unconnected-(IC2-RC4{slash}P1B{slash}C12OUT{slash}SRQ-Pad6)") (class "Default")
      (node (ref "IC2") (pin "6") (pinfunction "RC4/P1B/C12OUT/SRQ_6") (pintype "bidirectional"))
    )
    (net (code "80") (name "unconnected-(IC2-RC5{slash}CCP1{slash}P1A{slash}T0CKI-Pad5)") (class "Default")
      (node (ref "IC2") (pin "5") (pinfunction "RC5/CCP1/P1A/T0CKI_5") (pintype "bidirectional"))
    )
    (net (code "81") (name "unconnected-(IC2-RC6{slash}AN8{slash}~{SS{slash}T13CKI{slash}T1OSCI}-Pad8)") (class "Default")
      (node (ref "IC2") (pin "8") (pinfunction "RC6/AN8/~{SS/T13CKI/T1OSCI}_8") (pintype "bidirectional"))
    )
  )
)
